# Chaturayana_FIX.net
KiCad netlist of a schematic drawn in EAGLE
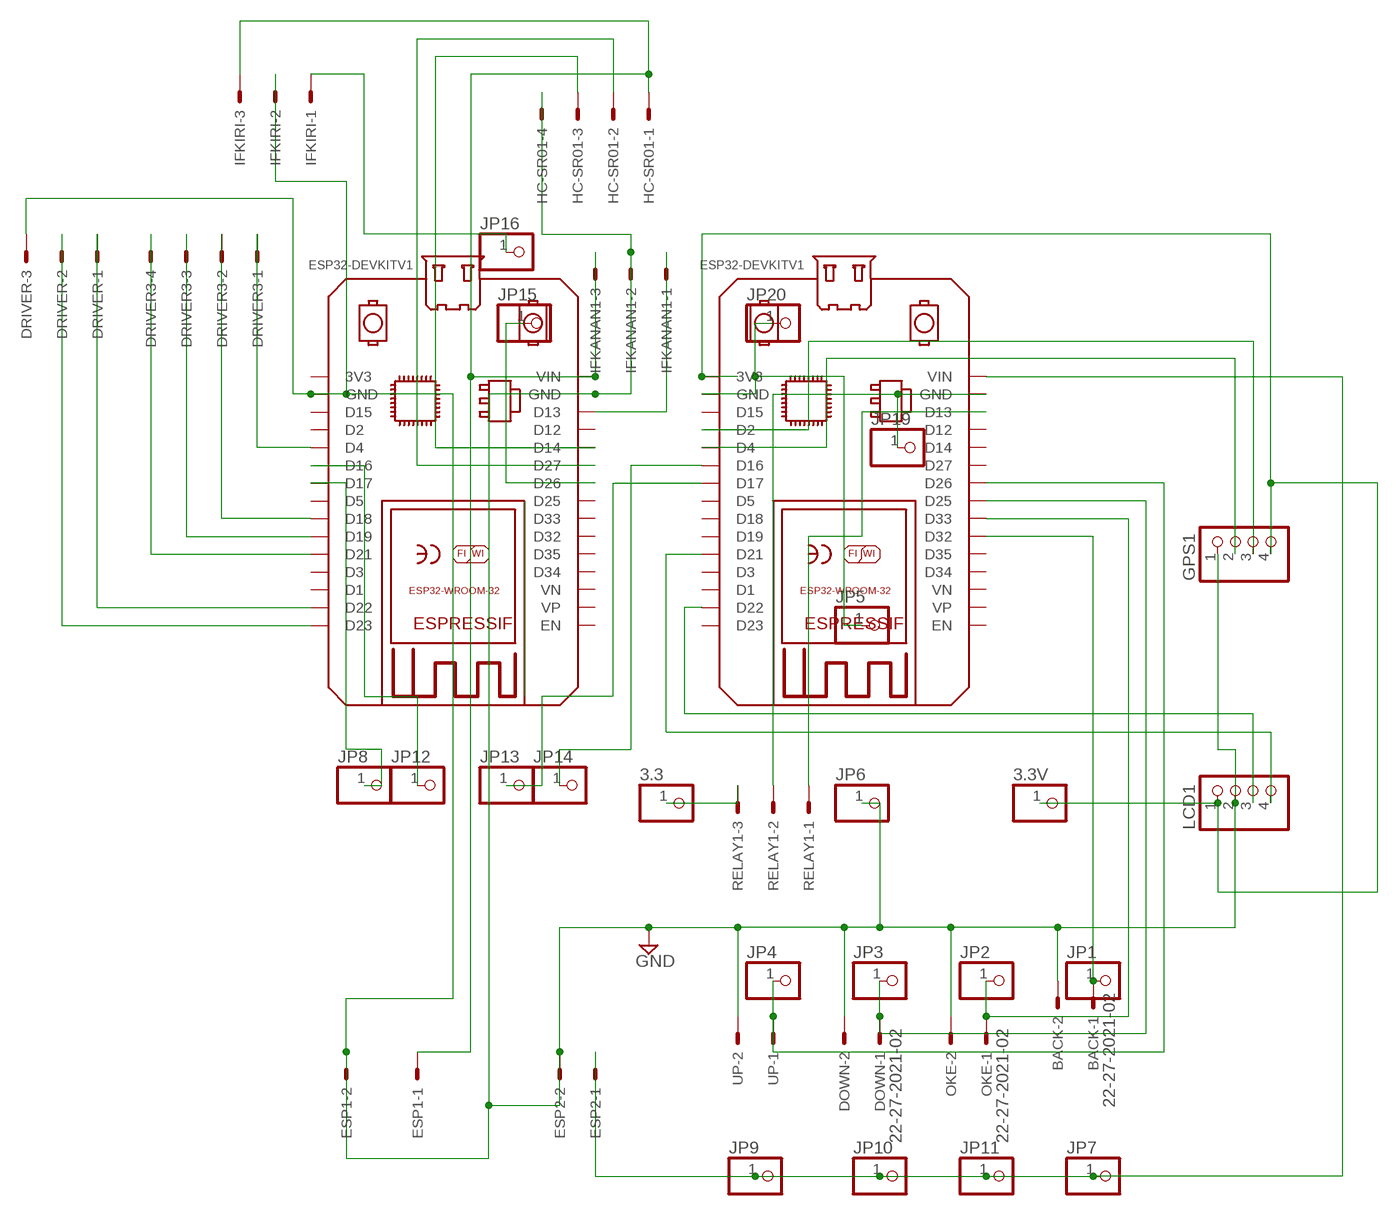
[diagram p0: schematic, sheet 1]

(export (version "E")
  (design (tool "Eeschema 10.0.6"))
  (components
    (comp (ref "3.3")
      (value "PINHD-1X1")
      (footprint "eagle-import:1X01")
      (libsource (lib "eagle-import") (part "PINHD-1X1"))
    )
    (comp (ref "3.3V")
      (value "PINHD-1X1")
      (footprint "eagle-import:1X01")
      (libsource (lib "eagle-import") (part "PINHD-1X1"))
    )
    (comp (ref "BACK")
      (value "22-27-2021-02")
      (footprint "eagle-import:6410-02")
      (fields (field (name "MF") "MOLEX"))
      (libsource (lib "eagle-import") (part "22-?-0227-2021"))
    )
    (comp (ref "BOARD2")
      (value "ESP32DEVKITV1")
      (footprint "eagle-import:ESP32-DEVKITV1")
      (libsource (lib "eagle-import") (part "ESP32DEVKITV1"))
    )
    (comp (ref "BOARD3")
      (value "ESP32DEVKITV1")
      (footprint "eagle-import:ESP32-DEVKITV1")
      (libsource (lib "eagle-import") (part "ESP32DEVKITV1"))
    )
    (comp (ref "DOWN")
      (value "22-27-2021-02")
      (footprint "eagle-import:6410-02")
      (fields (field (name "MF") "MOLEX"))
      (libsource (lib "eagle-import") (part "22-?-0227-2021"))
    )
    (comp (ref "DRIVER")
      (value "22-27-2031-03")
      (footprint "eagle-import:6410-03")
      (fields (field (name "MF") "MOLEX"))
      (libsource (lib "eagle-import") (part "22-?-0327-2031"))
    )
    (comp (ref "DRIVER3")
      (value "22-27-2041-04")
      (footprint "eagle-import:6410-04")
      (fields (field (name "MF") "MOLEX"))
      (libsource (lib "eagle-import") (part "22-?-0427-2041"))
    )
    (comp (ref "ESP1")
      (value "22-27-2021-02")
      (footprint "eagle-import:6410-02")
      (fields (field (name "MF") "MOLEX"))
      (libsource (lib "eagle-import") (part "22-?-0227-2021"))
    )
    (comp (ref "ESP2")
      (value "22-27-2021-02")
      (footprint "eagle-import:6410-02")
      (fields (field (name "MF") "MOLEX"))
      (libsource (lib "eagle-import") (part "22-?-0227-2021"))
    )
    (comp (ref "GPS1")
      (value "PINHD-1X4")
      (footprint "eagle-import:1X04")
      (libsource (lib "eagle-import") (part "PINHD-1X4"))
    )
    (comp (ref "HC-SR01")
      (value "22-27-2041-04")
      (footprint "eagle-import:6410-04")
      (fields (field (name "MF") "MOLEX"))
      (libsource (lib "eagle-import") (part "22-?-0427-2041"))
    )
    (comp (ref "IFKANAN1")
      (value "22-27-2031-03")
      (footprint "eagle-import:6410-03")
      (fields (field (name "MF") "MOLEX"))
      (libsource (lib "eagle-import") (part "22-?-0327-2031"))
    )
    (comp (ref "IFKIRI")
      (value "22-27-2031-03")
      (footprint "eagle-import:6410-03")
      (fields (field (name "MF") "MOLEX"))
      (libsource (lib "eagle-import") (part "22-?-0327-2031"))
    )
    (comp (ref "JP1")
      (value "PINHD-1X1")
      (footprint "eagle-import:1X01")
      (libsource (lib "eagle-import") (part "PINHD-1X1"))
    )
    (comp (ref "JP2")
      (value "PINHD-1X1")
      (footprint "eagle-import:1X01")
      (libsource (lib "eagle-import") (part "PINHD-1X1"))
    )
    (comp (ref "JP3")
      (value "PINHD-1X1")
      (footprint "eagle-import:1X01")
      (libsource (lib "eagle-import") (part "PINHD-1X1"))
    )
    (comp (ref "JP4")
      (value "PINHD-1X1")
      (footprint "eagle-import:1X01")
      (libsource (lib "eagle-import") (part "PINHD-1X1"))
    )
    (comp (ref "JP5")
      (value "PINHD-1X1")
      (footprint "eagle-import:1X01")
      (libsource (lib "eagle-import") (part "PINHD-1X1"))
    )
    (comp (ref "JP6")
      (value "PINHD-1X1")
      (footprint "eagle-import:1X01")
      (libsource (lib "eagle-import") (part "PINHD-1X1"))
    )
    (comp (ref "JP7")
      (value "PINHD-1X1")
      (footprint "eagle-import:1X01")
      (libsource (lib "eagle-import") (part "PINHD-1X1"))
    )
    (comp (ref "JP8")
      (value "PINHD-1X1")
      (footprint "eagle-import:1X01")
      (libsource (lib "eagle-import") (part "PINHD-1X1"))
    )
    (comp (ref "JP9")
      (value "PINHD-1X1")
      (footprint "eagle-import:1X01")
      (libsource (lib "eagle-import") (part "PINHD-1X1"))
    )
    (comp (ref "JP10")
      (value "PINHD-1X1")
      (footprint "eagle-import:1X01")
      (libsource (lib "eagle-import") (part "PINHD-1X1"))
    )
    (comp (ref "JP11")
      (value "PINHD-1X1")
      (footprint "eagle-import:1X01")
      (libsource (lib "eagle-import") (part "PINHD-1X1"))
    )
    (comp (ref "JP12")
      (value "PINHD-1X1")
      (footprint "eagle-import:1X01")
      (libsource (lib "eagle-import") (part "PINHD-1X1"))
    )
    (comp (ref "JP13")
      (value "PINHD-1X1")
      (footprint "eagle-import:1X01")
      (libsource (lib "eagle-import") (part "PINHD-1X1"))
    )
    (comp (ref "JP14")
      (value "PINHD-1X1")
      (footprint "eagle-import:1X01")
      (libsource (lib "eagle-import") (part "PINHD-1X1"))
    )
    (comp (ref "JP15")
      (value "PINHD-1X1")
      (footprint "eagle-import:1X01")
      (libsource (lib "eagle-import") (part "PINHD-1X1"))
    )
    (comp (ref "JP16")
      (value "PINHD-1X1")
      (footprint "eagle-import:1X01")
      (libsource (lib "eagle-import") (part "PINHD-1X1"))
    )
    (comp (ref "JP19")
      (value "PINHD-1X1")
      (footprint "eagle-import:1X01")
      (libsource (lib "eagle-import") (part "PINHD-1X1"))
    )
    (comp (ref "JP20")
      (value "PINHD-1X1")
      (footprint "eagle-import:1X01")
      (libsource (lib "eagle-import") (part "PINHD-1X1"))
    )
    (comp (ref "LCD1")
      (value "PINHD-1X4")
      (footprint "eagle-import:1X04")
      (libsource (lib "eagle-import") (part "PINHD-1X4"))
    )
    (comp (ref "OKE")
      (value "22-27-2021-02")
      (footprint "eagle-import:6410-02")
      (fields (field (name "MF") "MOLEX"))
      (libsource (lib "eagle-import") (part "22-?-0227-2021"))
    )
    (comp (ref "RELAY1")
      (value "22-27-2031-03")
      (footprint "eagle-import:6410-03")
      (fields (field (name "MF") "MOLEX"))
      (libsource (lib "eagle-import") (part "22-?-0327-2031"))
    )
    (comp (ref "UP")
      (value "22-27-2021-02")
      (footprint "eagle-import:6410-02")
      (fields (field (name "MF") "MOLEX"))
      (libsource (lib "eagle-import") (part "22-?-0227-2021"))
    )
  )
  (nets
    (net (code "1") (name "GND") (class "Default")
      (node (ref "BACK") (pin "2") (pinfunction "S_2") (pintype "passive"))
      (node (ref "BOARD2") (pin "GND") (pinfunction "GND_GND") (pintype "bidirectional"))
      (node (ref "BOARD2") (pin "GND@1") (pinfunction "GND_GND@1") (pintype "bidirectional"))
      (node (ref "DOWN") (pin "2") (pinfunction "S_2") (pintype "passive"))
      (node (ref "DRIVER") (pin "3") (pinfunction "S_3") (pintype "passive"))
      (node (ref "ESP1") (pin "2") (pinfunction "S_2") (pintype "passive"))
      (node (ref "ESP2") (pin "2") (pinfunction "S_2") (pintype "passive"))
      (node (ref "GPS1") (pin "1") (pinfunction "1_1") (pintype "passive"))
      (node (ref "HC-SR01") (pin "4") (pinfunction "S_4") (pintype "passive"))
      (node (ref "IFKANAN1") (pin "2") (pinfunction "S_2") (pintype "passive"))
      (node (ref "IFKIRI") (pin "2") (pinfunction "S_2") (pintype "passive"))
      (node (ref "JP6") (pin "1") (pinfunction "1_1") (pintype "passive"))
      (node (ref "LCD1") (pin "2") (pinfunction "2_2") (pintype "passive"))
      (node (ref "OKE") (pin "2") (pinfunction "S_2") (pintype "passive"))
      (node (ref "UP") (pin "2") (pinfunction "S_2") (pintype "passive"))
    )
    (net (code "2") (name "Net-(3.3V-Pad1)") (class "Default")
      (node (ref "3.3V") (pin "1") (pinfunction "1_1") (pintype "passive"))
      (node (ref "BOARD3") (pin "3V3") (pinfunction "3V3_3V3") (pintype "bidirectional"))
      (node (ref "GPS1") (pin "4") (pinfunction "4_4") (pintype "passive"))
      (node (ref "LCD1") (pin "1") (pinfunction "1_1") (pintype "passive"))
    )
    (net (code "3") (name "Net-(BACKA-S)") (class "Default")
      (node (ref "BACK") (pin "1") (pinfunction "S_1") (pintype "passive"))
      (node (ref "BOARD3") (pin "D32") (pinfunction "D32_D32") (pintype "bidirectional"))
      (node (ref "JP1") (pin "1") (pinfunction "1_1") (pintype "passive"))
    )
    (net (code "4") (name "Net-(BOARD2-PadD16)") (class "Default")
      (node (ref "BOARD2") (pin "D16") (pinfunction "D16_D16") (pintype "bidirectional"))
      (node (ref "JP12") (pin "1") (pinfunction "1_1") (pintype "passive"))
    )
    (net (code "5") (name "Net-(BOARD2-PadD17)") (class "Default")
      (node (ref "BOARD2") (pin "D17") (pinfunction "D17_D17") (pintype "bidirectional"))
      (node (ref "JP8") (pin "1") (pinfunction "1_1") (pintype "passive"))
    )
    (net (code "6") (name "Net-(BOARD2-PadD26)") (class "Default")
      (node (ref "BOARD2") (pin "D26") (pinfunction "D26_D26") (pintype "bidirectional"))
      (node (ref "JP15") (pin "1") (pinfunction "1_1") (pintype "passive"))
    )
    (net (code "7") (name "Net-(BOARD3-GND-PadGND@1)") (class "Default")
      (node (ref "BOARD3") (pin "GND@1") (pinfunction "GND_GND@1") (pintype "bidirectional"))
      (node (ref "JP20") (pin "1") (pinfunction "1_1") (pintype "passive"))
      (node (ref "JP5") (pin "1") (pinfunction "1_1") (pintype "passive"))
    )
    (net (code "8") (name "Net-(BOARD3-PadD2)") (class "Default")
      (node (ref "BOARD3") (pin "D2") (pinfunction "D2_D2") (pintype "bidirectional"))
      (node (ref "GPS1") (pin "3") (pinfunction "3_3") (pintype "passive"))
    )
    (net (code "9") (name "Net-(BOARD3-PadD4)") (class "Default")
      (node (ref "BOARD3") (pin "D4") (pinfunction "D4_D4") (pintype "bidirectional"))
      (node (ref "GPS1") (pin "2") (pinfunction "2_2") (pintype "passive"))
    )
    (net (code "10") (name "Net-(BOARD3-PadD16)") (class "Default")
      (node (ref "BOARD3") (pin "D16") (pinfunction "D16_D16") (pintype "bidirectional"))
      (node (ref "JP14") (pin "1") (pinfunction "1_1") (pintype "passive"))
    )
    (net (code "11") (name "Net-(BOARD3-PadD17)") (class "Default")
      (node (ref "BOARD3") (pin "D17") (pinfunction "D17_D17") (pintype "bidirectional"))
      (node (ref "JP13") (pin "1") (pinfunction "1_1") (pintype "passive"))
    )
    (net (code "12") (name "Net-(BOARD3-PadD21)") (class "Default")
      (node (ref "BOARD3") (pin "D21") (pinfunction "D21_D21") (pintype "bidirectional"))
      (node (ref "LCD1") (pin "4") (pinfunction "4_4") (pintype "passive"))
    )
    (net (code "13") (name "Net-(BOARD3-PadD22)") (class "Default")
      (node (ref "BOARD3") (pin "D22") (pinfunction "D22_D22") (pintype "bidirectional"))
      (node (ref "LCD1") (pin "3") (pinfunction "3_3") (pintype "passive"))
    )
    (net (code "14") (name "Net-(DOWNA-S)") (class "Default")
      (node (ref "BOARD3") (pin "D25") (pinfunction "D25_D25") (pintype "bidirectional"))
      (node (ref "DOWN") (pin "1") (pinfunction "S_1") (pintype "passive"))
      (node (ref "JP3") (pin "1") (pinfunction "1_1") (pintype "passive"))
    )
    (net (code "15") (name "Net-(DRIVER3A-S)") (class "Default")
      (node (ref "BOARD2") (pin "D4") (pinfunction "D4_D4") (pintype "bidirectional"))
      (node (ref "DRIVER3") (pin "1") (pinfunction "S_1") (pintype "passive"))
    )
    (net (code "16") (name "Net-(DRIVER3B-S)") (class "Default")
      (node (ref "BOARD2") (pin "D18") (pinfunction "D18_D18") (pintype "bidirectional"))
      (node (ref "DRIVER3") (pin "2") (pinfunction "S_2") (pintype "passive"))
    )
    (net (code "17") (name "Net-(DRIVER3C-S)") (class "Default")
      (node (ref "BOARD2") (pin "D19") (pinfunction "D19_D19") (pintype "bidirectional"))
      (node (ref "DRIVER3") (pin "3") (pinfunction "S_3") (pintype "passive"))
    )
    (net (code "18") (name "Net-(DRIVER3D-S)") (class "Default")
      (node (ref "BOARD2") (pin "D21") (pinfunction "D21_D21") (pintype "bidirectional"))
      (node (ref "DRIVER3") (pin "4") (pinfunction "S_4") (pintype "passive"))
    )
    (net (code "19") (name "Net-(DRIVERA-S)") (class "Default")
      (node (ref "BOARD2") (pin "D22") (pinfunction "D22_D22") (pintype "bidirectional"))
      (node (ref "DRIVER") (pin "1") (pinfunction "S_1") (pintype "passive"))
    )
    (net (code "20") (name "Net-(DRIVERB-S)") (class "Default")
      (node (ref "BOARD2") (pin "D23") (pinfunction "D23_D23") (pintype "bidirectional"))
      (node (ref "DRIVER") (pin "2") (pinfunction "S_2") (pintype "passive"))
    )
    (net (code "21") (name "Net-(ESP1A-S)") (class "Default")
      (node (ref "BOARD2") (pin "VIN") (pinfunction "VIN_VIN") (pintype "bidirectional"))
      (node (ref "ESP1") (pin "1") (pinfunction "S_1") (pintype "passive"))
      (node (ref "HC-SR01") (pin "1") (pinfunction "S_1") (pintype "passive"))
      (node (ref "IFKANAN1") (pin "3") (pinfunction "S_3") (pintype "passive"))
      (node (ref "IFKIRI") (pin "3") (pinfunction "S_3") (pintype "passive"))
    )
    (net (code "22") (name "Net-(ESP2A-S)") (class "Default")
      (node (ref "BOARD3") (pin "VIN") (pinfunction "VIN_VIN") (pintype "bidirectional"))
      (node (ref "ESP2") (pin "1") (pinfunction "S_1") (pintype "passive"))
      (node (ref "JP10") (pin "1") (pinfunction "1_1") (pintype "passive"))
      (node (ref "JP11") (pin "1") (pinfunction "1_1") (pintype "passive"))
      (node (ref "JP7") (pin "1") (pinfunction "1_1") (pintype "passive"))
      (node (ref "JP9") (pin "1") (pinfunction "1_1") (pintype "passive"))
    )
    (net (code "23") (name "Net-(HC-SR01B-S)") (class "Default")
      (node (ref "BOARD2") (pin "D27") (pinfunction "D27_D27") (pintype "bidirectional"))
      (node (ref "HC-SR01") (pin "2") (pinfunction "S_2") (pintype "passive"))
    )
    (net (code "24") (name "Net-(HC-SR01C-S)") (class "Default")
      (node (ref "BOARD2") (pin "D14") (pinfunction "D14_D14") (pintype "bidirectional"))
      (node (ref "HC-SR01") (pin "3") (pinfunction "S_3") (pintype "passive"))
    )
    (net (code "25") (name "Net-(IFKANAN1A-S)") (class "Default")
      (node (ref "BOARD2") (pin "D13") (pinfunction "D13_D13") (pintype "bidirectional"))
      (node (ref "IFKANAN1") (pin "1") (pinfunction "S_1") (pintype "passive"))
    )
    (net (code "26") (name "Net-(IFKIRIA-S)") (class "Default")
      (node (ref "IFKIRI") (pin "1") (pinfunction "S_1") (pintype "passive"))
      (node (ref "JP16") (pin "1") (pinfunction "1_1") (pintype "passive"))
    )
    (net (code "27") (name "Net-(OKEA-S)") (class "Default")
      (node (ref "BOARD3") (pin "D33") (pinfunction "D33_D33") (pintype "bidirectional"))
      (node (ref "JP2") (pin "1") (pinfunction "1_1") (pintype "passive"))
      (node (ref "OKE") (pin "1") (pinfunction "S_1") (pintype "passive"))
    )
    (net (code "28") (name "Net-(RELAY1A-S)") (class "Default")
      (node (ref "BOARD3") (pin "D13") (pinfunction "D13_D13") (pintype "bidirectional"))
      (node (ref "RELAY1") (pin "1") (pinfunction "S_1") (pintype "passive"))
    )
    (net (code "29") (name "Net-(RELAY1B-S)") (class "Default")
      (node (ref "BOARD3") (pin "GND") (pinfunction "GND_GND") (pintype "bidirectional"))
      (node (ref "JP19") (pin "1") (pinfunction "1_1") (pintype "passive"))
      (node (ref "RELAY1") (pin "2") (pinfunction "S_2") (pintype "passive"))
    )
    (net (code "30") (name "Net-(RELAY1C-S)") (class "Default")
      (node (ref "3.3") (pin "1") (pinfunction "1_1") (pintype "passive"))
      (node (ref "RELAY1") (pin "3") (pinfunction "S_3") (pintype "passive"))
    )
    (net (code "31") (name "Net-(UPA-S)") (class "Default")
      (node (ref "BOARD3") (pin "D26") (pinfunction "D26_D26") (pintype "bidirectional"))
      (node (ref "JP4") (pin "1") (pinfunction "1_1") (pintype "passive"))
      (node (ref "UP") (pin "1") (pinfunction "S_1") (pintype "passive"))
    )
    (net (code "32") (name "unconnected-(BOARD2-Pad3V3)") (class "Default")
      (node (ref "BOARD2") (pin "3V3") (pinfunction "3V3_3V3") (pintype "bidirectional"))
    )
    (net (code "33") (name "unconnected-(BOARD2-PadD1)") (class "Default")
      (node (ref "BOARD2") (pin "D1") (pinfunction "D1_D1") (pintype "bidirectional"))
    )
    (net (code "34") (name "unconnected-(BOARD2-PadD2)") (class "Default")
      (node (ref "BOARD2") (pin "D2") (pinfunction "D2_D2") (pintype "bidirectional"))
    )
    (net (code "35") (name "unconnected-(BOARD2-PadD3)") (class "Default")
      (node (ref "BOARD2") (pin "D3") (pinfunction "D3_D3") (pintype "bidirectional"))
    )
    (net (code "36") (name "unconnected-(BOARD2-PadD5)") (class "Default")
      (node (ref "BOARD2") (pin "D5") (pinfunction "D5_D5") (pintype "bidirectional"))
    )
    (net (code "37") (name "unconnected-(BOARD2-PadD12)") (class "Default")
      (node (ref "BOARD2") (pin "D12") (pinfunction "D12_D12") (pintype "bidirectional"))
    )
    (net (code "38") (name "unconnected-(BOARD2-PadD15)") (class "Default")
      (node (ref "BOARD2") (pin "D15") (pinfunction "D15_D15") (pintype "bidirectional"))
    )
    (net (code "39") (name "unconnected-(BOARD2-PadD25)") (class "Default")
      (node (ref "BOARD2") (pin "D25") (pinfunction "D25_D25") (pintype "bidirectional"))
    )
    (net (code "40") (name "unconnected-(BOARD2-PadD32)") (class "Default")
      (node (ref "BOARD2") (pin "D32") (pinfunction "D32_D32") (pintype "bidirectional"))
    )
    (net (code "41") (name "unconnected-(BOARD2-PadD33)") (class "Default")
      (node (ref "BOARD2") (pin "D33") (pinfunction "D33_D33") (pintype "bidirectional"))
    )
    (net (code "42") (name "unconnected-(BOARD2-PadD34)") (class "Default")
      (node (ref "BOARD2") (pin "D34") (pinfunction "D34_D34") (pintype "bidirectional"))
    )
    (net (code "43") (name "unconnected-(BOARD2-PadD35)") (class "Default")
      (node (ref "BOARD2") (pin "D35") (pinfunction "D35_D35") (pintype "bidirectional"))
    )
    (net (code "44") (name "unconnected-(BOARD2-PadEN)") (class "Default")
      (node (ref "BOARD2") (pin "EN") (pinfunction "EN_EN") (pintype "bidirectional"))
    )
    (net (code "45") (name "unconnected-(BOARD2-PadVN)") (class "Default")
      (node (ref "BOARD2") (pin "VN") (pinfunction "VN_VN") (pintype "bidirectional"))
    )
    (net (code "46") (name "unconnected-(BOARD2-PadVP)") (class "Default")
      (node (ref "BOARD2") (pin "VP") (pinfunction "VP_VP") (pintype "bidirectional"))
    )
    (net (code "47") (name "unconnected-(BOARD3-PadD1)") (class "Default")
      (node (ref "BOARD3") (pin "D1") (pinfunction "D1_D1") (pintype "bidirectional"))
    )
    (net (code "48") (name "unconnected-(BOARD3-PadD3)") (class "Default")
      (node (ref "BOARD3") (pin "D3") (pinfunction "D3_D3") (pintype "bidirectional"))
    )
    (net (code "49") (name "unconnected-(BOARD3-PadD5)") (class "Default")
      (node (ref "BOARD3") (pin "D5") (pinfunction "D5_D5") (pintype "bidirectional"))
    )
    (net (code "50") (name "unconnected-(BOARD3-PadD12)") (class "Default")
      (node (ref "BOARD3") (pin "D12") (pinfunction "D12_D12") (pintype "bidirectional"))
    )
    (net (code "51") (name "unconnected-(BOARD3-PadD14)") (class "Default")
      (node (ref "BOARD3") (pin "D14") (pinfunction "D14_D14") (pintype "bidirectional"))
    )
    (net (code "52") (name "unconnected-(BOARD3-PadD15)") (class "Default")
      (node (ref "BOARD3") (pin "D15") (pinfunction "D15_D15") (pintype "bidirectional"))
    )
    (net (code "53") (name "unconnected-(BOARD3-PadD18)") (class "Default")
      (node (ref "BOARD3") (pin "D18") (pinfunction "D18_D18") (pintype "bidirectional"))
    )
    (net (code "54") (name "unconnected-(BOARD3-PadD19)") (class "Default")
      (node (ref "BOARD3") (pin "D19") (pinfunction "D19_D19") (pintype "bidirectional"))
    )
    (net (code "55") (name "unconnected-(BOARD3-PadD23)") (class "Default")
      (node (ref "BOARD3") (pin "D23") (pinfunction "D23_D23") (pintype "bidirectional"))
    )
    (net (code "56") (name "unconnected-(BOARD3-PadD27)") (class "Default")
      (node (ref "BOARD3") (pin "D27") (pinfunction "D27_D27") (pintype "bidirectional"))
    )
    (net (code "57") (name "unconnected-(BOARD3-PadD34)") (class "Default")
      (node (ref "BOARD3") (pin "D34") (pinfunction "D34_D34") (pintype "bidirectional"))
    )
    (net (code "58") (name "unconnected-(BOARD3-PadD35)") (class "Default")
      (node (ref "BOARD3") (pin "D35") (pinfunction "D35_D35") (pintype "bidirectional"))
    )
    (net (code "59") (name "unconnected-(BOARD3-PadEN)") (class "Default")
      (node (ref "BOARD3") (pin "EN") (pinfunction "EN_EN") (pintype "bidirectional"))
    )
    (net (code "60") (name "unconnected-(BOARD3-PadVN)") (class "Default")
      (node (ref "BOARD3") (pin "VN") (pinfunction "VN_VN") (pintype "bidirectional"))
    )
    (net (code "61") (name "unconnected-(BOARD3-PadVP)") (class "Default")
      (node (ref "BOARD3") (pin "VP") (pinfunction "VP_VP") (pintype "bidirectional"))
    )
  )
)
